# dIRKey.net
KiCad netlist of a schematic drawn in EAGLE
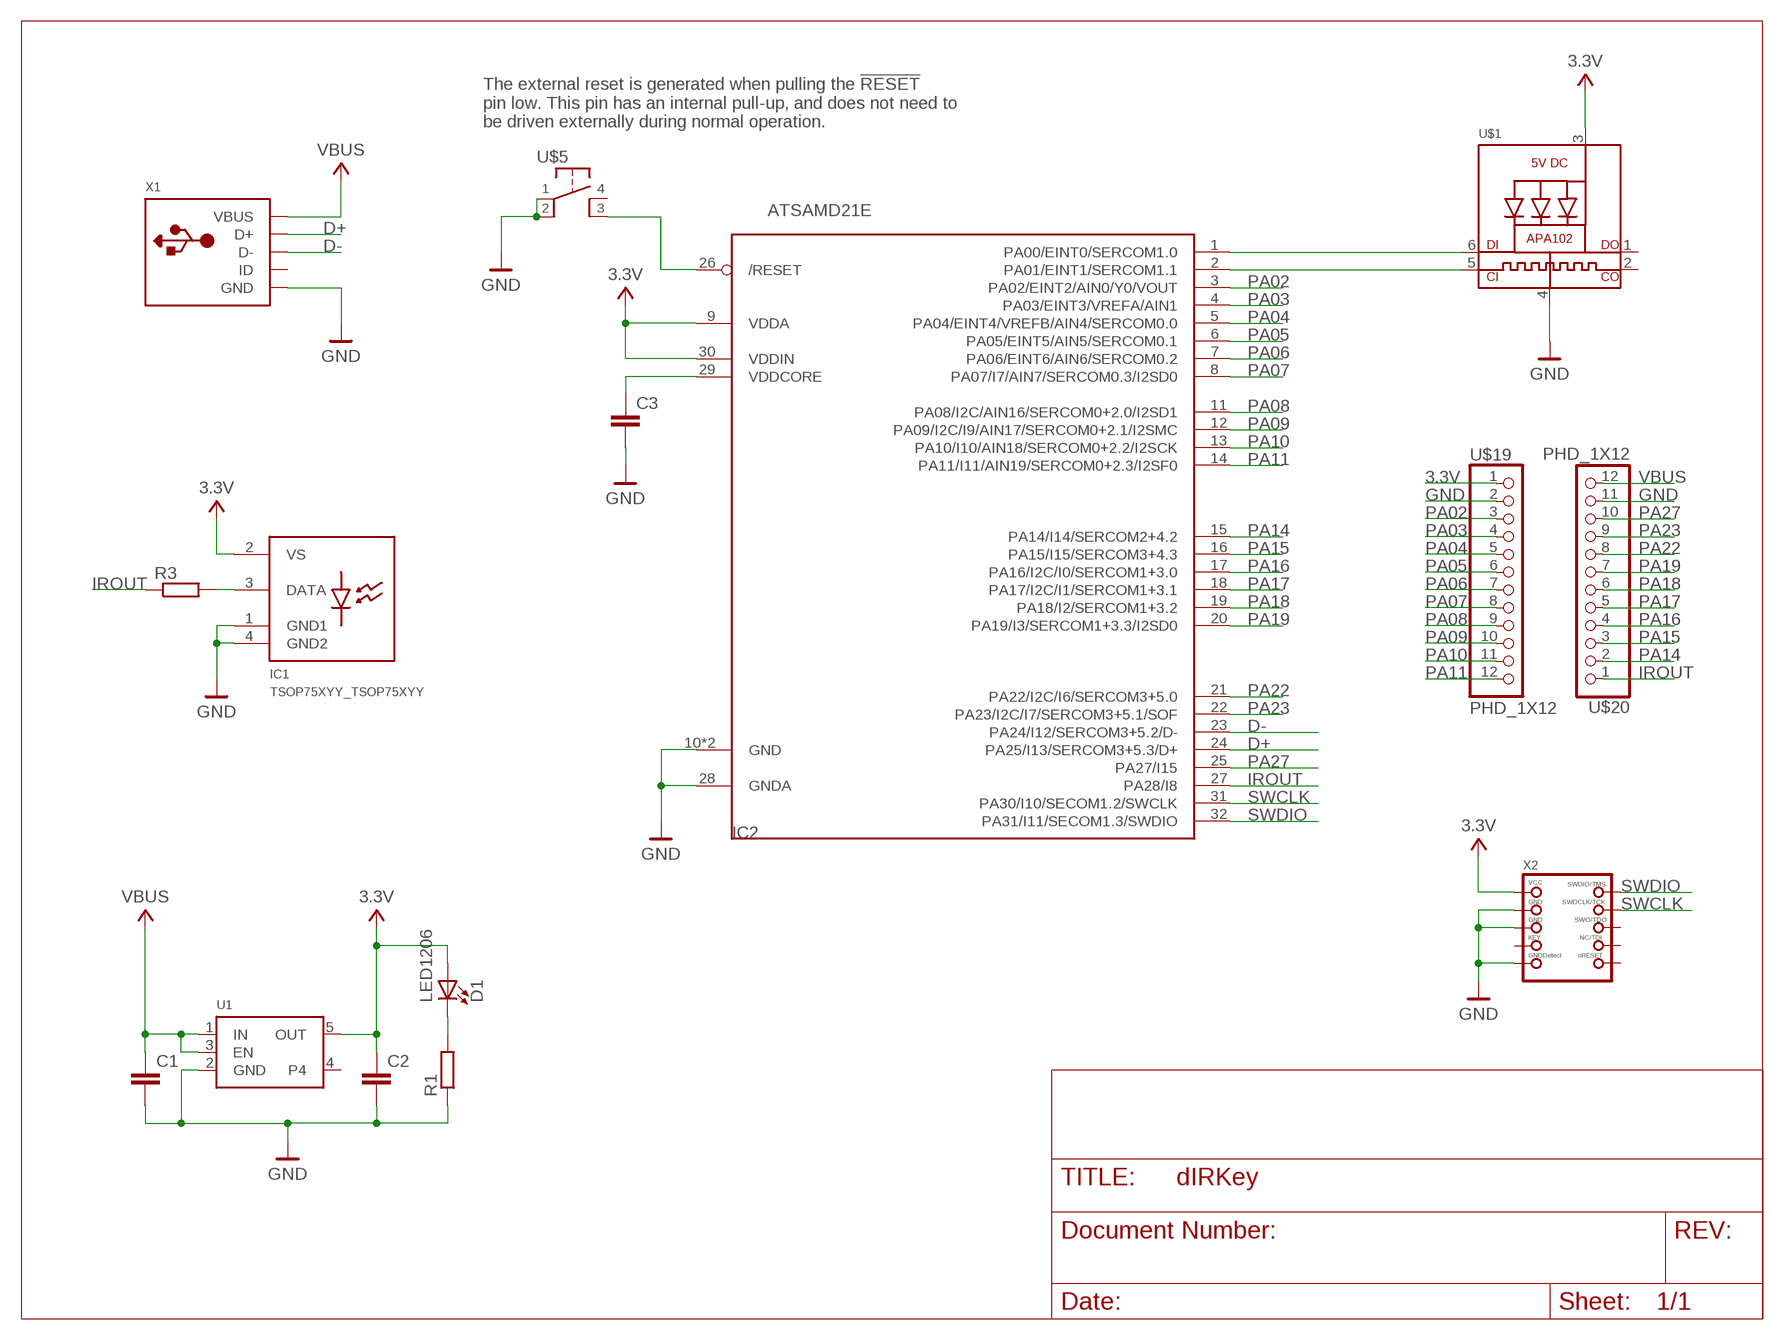
[diagram p0: schematic, sheet 1]

(export (version "E")
  (design (tool "Eeschema 10.0.6"))
  (components
    (comp (ref "C1")
      (value "C-EUC1206")
      (footprint "eagle-import:C1206")
      (libsource (lib "eagle-import") (part "C-EUC1206"))
    )
    (comp (ref "C2")
      (value "C-EUC1206")
      (footprint "eagle-import:C1206")
      (libsource (lib "eagle-import") (part "C-EUC1206"))
    )
    (comp (ref "C3")
      (value "C-EUC1206")
      (footprint "eagle-import:C1206")
      (libsource (lib "eagle-import") (part "C-EUC1206"))
    )
    (comp (ref "D1")
      (value "LED1206")
      (footprint "eagle-import:LED1206")
      (libsource (lib "eagle-import") (part "LED1206"))
    )
    (comp (ref "IC1")
      (value "TSOP75XYY_TSOP75XYY")
      (footprint "eagle-import:TSOP75XYY_TSOP75XYY")
      (libsource (lib "eagle-import") (part "TSOP75XYY_TSOP75XYY"))
    )
    (comp (ref "IC2")
      (value "ATSAMD21E")
      (footprint "eagle-import:QFN32_5MM")
      (libsource (lib "eagle-import") (part "ATSAMD21E"))
    )
    (comp (ref "R1")
      (value "R-EU_R1206")
      (footprint "eagle-import:R1206")
      (libsource (lib "eagle-import") (part "R-EU_R1206"))
    )
    (comp (ref "R3")
      (value "R-EU_R1206")
      (footprint "eagle-import:R1206")
      (libsource (lib "eagle-import") (part "R-EU_R1206"))
    )
    (comp (ref "U$1")
      (value "DOTSTAR_APA1022020")
      (footprint "eagle-import:APA102_2020")
      (libsource (lib "eagle-import") (part "DOTSTAR_APA1022020"))
    )
    (comp (ref "U$5")
      (value "PTS647")
      (footprint "eagle-import:PTS647")
      (libsource (lib "eagle-import") (part "PTS647"))
    )
    (comp (ref "U$19")
      (value "PHD_1X12")
      (footprint "eagle-import:PHD_1X12")
      (libsource (lib "eagle-import") (part "PHD_1X12"))
    )
    (comp (ref "U$20")
      (value "PHD_1X12")
      (footprint "eagle-import:PHD_1X12")
      (libsource (lib "eagle-import") (part "PHD_1X12"))
    )
    (comp (ref "U1")
      (value "AP2112K")
      (footprint "eagle-import:SOT23-5")
      (libsource (lib "eagle-import") (part "AP2112K"))
    )
    (comp (ref "X1")
      (value "USB_MICRO_BMICRO_20329")
      (footprint "eagle-import:USB_MICRO_B")
      (libsource (lib "eagle-import") (part "USB_MICRO_BMICRO_20329"))
    )
    (comp (ref "X2")
      (value "SWD_2X5")
      (footprint "eagle-import:SWD_MINI")
      (libsource (lib "eagle-import") (part "SWD_2X5"))
    )
  )
  (nets
    (net (code "1") (name "/D+") (class "Default")
      (node (ref "IC2") (pin "24") (pinfunction "PA25/I13/SERCOM3+5.3/D+_24") (pintype "bidirectional"))
      (node (ref "X1") (pin "D+") (pinfunction "D+_D+") (pintype "bidirectional"))
    )
    (net (code "2") (name "/D-") (class "Default")
      (node (ref "IC2") (pin "23") (pinfunction "PA24/I12/SERCOM3+5.2/D-_23") (pintype "bidirectional"))
      (node (ref "X1") (pin "D-") (pinfunction "D-_D-") (pintype "bidirectional"))
    )
    (net (code "3") (name "/IROUT") (class "Default")
      (node (ref "IC2") (pin "27") (pinfunction "PA28/I8_27") (pintype "bidirectional"))
      (node (ref "R3") (pin "1") (pinfunction "1_1") (pintype "passive"))
      (node (ref "U$20") (pin "1") (pinfunction "1_1") (pintype "passive"))
    )
    (net (code "4") (name "/PA02") (class "Default")
      (node (ref "IC2") (pin "3") (pinfunction "PA02/EINT2/AIN0/Y0/VOUT_3") (pintype "bidirectional"))
      (node (ref "U$19") (pin "3") (pinfunction "3_3") (pintype "passive"))
    )
    (net (code "5") (name "/PA03") (class "Default")
      (node (ref "IC2") (pin "4") (pinfunction "PA03/EINT3/VREFA/AIN1_4") (pintype "bidirectional"))
      (node (ref "U$19") (pin "4") (pinfunction "4_4") (pintype "passive"))
    )
    (net (code "6") (name "/PA04") (class "Default")
      (node (ref "IC2") (pin "5") (pinfunction "PA04/EINT4/VREFB/AIN4/SERCOM0.0_5") (pintype "bidirectional"))
      (node (ref "U$19") (pin "5") (pinfunction "5_5") (pintype "passive"))
    )
    (net (code "7") (name "/PA05") (class "Default")
      (node (ref "IC2") (pin "6") (pinfunction "PA05/EINT5/AIN5/SERCOM0.1_6") (pintype "bidirectional"))
      (node (ref "U$19") (pin "6") (pinfunction "6_6") (pintype "passive"))
    )
    (net (code "8") (name "/PA06") (class "Default")
      (node (ref "IC2") (pin "7") (pinfunction "PA06/EINT6/AIN6/SERCOM0.2_7") (pintype "bidirectional"))
      (node (ref "U$19") (pin "7") (pinfunction "7_7") (pintype "passive"))
    )
    (net (code "9") (name "/PA07") (class "Default")
      (node (ref "IC2") (pin "8") (pinfunction "PA07/I7/AIN7/SERCOM0.3/I2SD0_8") (pintype "bidirectional"))
      (node (ref "U$19") (pin "8") (pinfunction "8_8") (pintype "passive"))
    )
    (net (code "10") (name "/PA08") (class "Default")
      (node (ref "IC2") (pin "11") (pinfunction "PA08/I2C/AIN16/SERCOM0+2.0/I2SD1_11") (pintype "bidirectional"))
      (node (ref "U$19") (pin "9") (pinfunction "9_9") (pintype "passive"))
    )
    (net (code "11") (name "/PA09") (class "Default")
      (node (ref "IC2") (pin "12") (pinfunction "PA09/I2C/I9/AIN17/SERCOM0+2.1/I2SMC_12") (pintype "bidirectional"))
      (node (ref "U$19") (pin "10") (pinfunction "10_10") (pintype "passive"))
    )
    (net (code "12") (name "/PA10") (class "Default")
      (node (ref "IC2") (pin "13") (pinfunction "PA10/I10/AIN18/SERCOM0+2.2/I2SCK_13") (pintype "bidirectional"))
      (node (ref "U$19") (pin "11") (pinfunction "11_11") (pintype "passive"))
    )
    (net (code "13") (name "/PA11") (class "Default")
      (node (ref "IC2") (pin "14") (pinfunction "PA11/I11/AIN19/SERCOM0+2.3/I2SF0_14") (pintype "bidirectional"))
      (node (ref "U$19") (pin "12") (pinfunction "12_12") (pintype "passive"))
    )
    (net (code "14") (name "/PA14") (class "Default")
      (node (ref "IC2") (pin "15") (pinfunction "PA14/I14/SERCOM2+4.2_15") (pintype "bidirectional"))
      (node (ref "U$20") (pin "2") (pinfunction "2_2") (pintype "passive"))
    )
    (net (code "15") (name "/PA15") (class "Default")
      (node (ref "IC2") (pin "16") (pinfunction "PA15/I15/SERCOM3+4.3_16") (pintype "bidirectional"))
      (node (ref "U$20") (pin "3") (pinfunction "3_3") (pintype "passive"))
    )
    (net (code "16") (name "/PA16") (class "Default")
      (node (ref "IC2") (pin "17") (pinfunction "PA16/I2C/I0/SERCOM1+3.0_17") (pintype "bidirectional"))
      (node (ref "U$20") (pin "4") (pinfunction "4_4") (pintype "passive"))
    )
    (net (code "17") (name "/PA17") (class "Default")
      (node (ref "IC2") (pin "18") (pinfunction "PA17/I2C/I1/SERCOM1+3.1_18") (pintype "bidirectional"))
      (node (ref "U$20") (pin "5") (pinfunction "5_5") (pintype "passive"))
    )
    (net (code "18") (name "/PA18") (class "Default")
      (node (ref "IC2") (pin "19") (pinfunction "PA18/I2/SERCOM1+3.2_19") (pintype "bidirectional"))
      (node (ref "U$20") (pin "6") (pinfunction "6_6") (pintype "passive"))
    )
    (net (code "19") (name "/PA19") (class "Default")
      (node (ref "IC2") (pin "20") (pinfunction "PA19/I3/SERCOM1+3.3/I2SD0_20") (pintype "bidirectional"))
      (node (ref "U$20") (pin "7") (pinfunction "7_7") (pintype "passive"))
    )
    (net (code "20") (name "/PA22") (class "Default")
      (node (ref "IC2") (pin "21") (pinfunction "PA22/I2C/I6/SERCOM3+5.0_21") (pintype "bidirectional"))
      (node (ref "U$20") (pin "8") (pinfunction "8_8") (pintype "passive"))
    )
    (net (code "21") (name "/PA23") (class "Default")
      (node (ref "IC2") (pin "22") (pinfunction "PA23/I2C/I7/SERCOM3+5.1/SOF_22") (pintype "bidirectional"))
      (node (ref "U$20") (pin "9") (pinfunction "9_9") (pintype "passive"))
    )
    (net (code "22") (name "/PA27") (class "Default")
      (node (ref "IC2") (pin "25") (pinfunction "PA27/I15_25") (pintype "bidirectional"))
      (node (ref "U$20") (pin "10") (pinfunction "10_10") (pintype "passive"))
    )
    (net (code "23") (name "/SWCLK") (class "Default")
      (node (ref "IC2") (pin "31") (pinfunction "PA30/I10/SECOM1.2/SWCLK_31") (pintype "bidirectional"))
      (node (ref "X2") (pin "4") (pinfunction "SWDCLK_4") (pintype "bidirectional"))
    )
    (net (code "24") (name "/SWDIO") (class "Default")
      (node (ref "IC2") (pin "32") (pinfunction "PA31/I11/SECOM1.3/SWDIO_32") (pintype "bidirectional"))
      (node (ref "X2") (pin "2") (pinfunction "SWDIO_2") (pintype "bidirectional"))
    )
    (net (code "25") (name "3.3V") (class "Default")
      (node (ref "C2") (pin "1") (pinfunction "1_1") (pintype "passive"))
      (node (ref "D1") (pin "2") (pinfunction "A_2") (pintype "passive"))
      (node (ref "IC1") (pin "2") (pinfunction "VS_2") (pintype "passive"))
      (node (ref "IC2") (pin "30") (pinfunction "VDDIN_30") (pintype "power_in"))
      (node (ref "IC2") (pin "9") (pinfunction "VDDA_9") (pintype "power_in"))
      (node (ref "U$1") (pin "3") (pinfunction "VDD_3") (pintype "power_in"))
      (node (ref "U$19") (pin "1") (pinfunction "1_1") (pintype "passive"))
      (node (ref "U1") (pin "5") (pinfunction "OUT_5") (pintype "power_in"))
      (node (ref "X2") (pin "1") (pinfunction "VCC_1") (pintype "power_in"))
    )
    (net (code "26") (name "GND") (class "Default")
      (node (ref "C1") (pin "2") (pinfunction "2_2") (pintype "passive"))
      (node (ref "C2") (pin "2") (pinfunction "2_2") (pintype "passive"))
      (node (ref "C3") (pin "2") (pinfunction "2_2") (pintype "passive"))
      (node (ref "IC1") (pin "1") (pinfunction "GND1_1") (pintype "passive"))
      (node (ref "IC1") (pin "4") (pinfunction "GND2_4") (pintype "passive"))
      (node (ref "IC2") (pin "10") (pinfunction "GND_10") (pintype "power_in"))
      (node (ref "IC2") (pin "28") (pinfunction "GNDA_28") (pintype "power_in"))
      (node (ref "IC2") (pin "33") (pinfunction "GND_33") (pintype "power_in"))
      (node (ref "R1") (pin "1") (pinfunction "1_1") (pintype "passive"))
      (node (ref "U$1") (pin "4") (pinfunction "GND_4") (pintype "power_in"))
      (node (ref "U$19") (pin "2") (pinfunction "2_2") (pintype "passive"))
      (node (ref "U$20") (pin "11") (pinfunction "11_11") (pintype "passive"))
      (node (ref "U$5") (pin "1") (pinfunction "1_1") (pintype "bidirectional"))
      (node (ref "U$5") (pin "2") (pinfunction "2_2") (pintype "bidirectional"))
      (node (ref "U1") (pin "2") (pinfunction "GND_2") (pintype "power_in"))
      (node (ref "X1") (pin "BASE@1") (pinfunction "GND_BASE@1") (pintype "power_in"))
      (node (ref "X1") (pin "BASE@2") (pinfunction "GND_BASE@2") (pintype "power_in"))
      (node (ref "X1") (pin "GND") (pinfunction "GND_GND") (pintype "power_in"))
      (node (ref "X1") (pin "SPRT@1") (pinfunction "GND_SPRT@1") (pintype "power_in"))
      (node (ref "X1") (pin "SPRT@2") (pinfunction "GND_SPRT@2") (pintype "power_in"))
      (node (ref "X1") (pin "SPRT@3") (pinfunction "GND_SPRT@3") (pintype "power_in"))
      (node (ref "X1") (pin "SPRT@4") (pinfunction "GND_SPRT@4") (pintype "power_in"))
      (node (ref "X2") (pin "3") (pinfunction "GND_3") (pintype "power_in"))
      (node (ref "X2") (pin "5") (pinfunction "GND_5") (pintype "power_in"))
      (node (ref "X2") (pin "9") (pinfunction "GNDDETECT_9") (pintype "bidirectional"))
    )
    (net (code "27") (name "Net-(D1-C)") (class "Default")
      (node (ref "D1") (pin "1") (pinfunction "C_1") (pintype "passive"))
      (node (ref "R1") (pin "2") (pinfunction "2_2") (pintype "passive"))
    )
    (net (code "28") (name "Net-(IC1-DATA)") (class "Default")
      (node (ref "IC1") (pin "3") (pinfunction "DATA_3") (pintype "output"))
      (node (ref "R3") (pin "2") (pinfunction "2_2") (pintype "passive"))
    )
    (net (code "29") (name "Net-(IC2-PA00{slash}EINT0{slash}SERCOM1.0)") (class "Default")
      (node (ref "IC2") (pin "1") (pinfunction "PA00/EINT0/SERCOM1.0_1") (pintype "bidirectional"))
      (node (ref "U$1") (pin "6") (pinfunction "DI_6") (pintype "input"))
    )
    (net (code "30") (name "Net-(IC2-PA01{slash}EINT1{slash}SERCOM1.1)") (class "Default")
      (node (ref "IC2") (pin "2") (pinfunction "PA01/EINT1/SERCOM1.1_2") (pintype "bidirectional"))
      (node (ref "U$1") (pin "5") (pinfunction "CKI_5") (pintype "input"))
    )
    (net (code "31") (name "Net-(IC2-VDDCORE)") (class "Default")
      (node (ref "C3") (pin "1") (pinfunction "1_1") (pintype "passive"))
      (node (ref "IC2") (pin "29") (pinfunction "VDDCORE_29") (pintype "power_in"))
    )
    (net (code "32") (name "Net-(IC2-{slash}RESET)") (class "Default")
      (node (ref "IC2") (pin "26") (pinfunction "/RESET_26") (pintype "bidirectional"))
      (node (ref "U$5") (pin "3") (pinfunction "3_3") (pintype "bidirectional"))
    )
    (net (code "33") (name "VBUS") (class "Default")
      (node (ref "C1") (pin "1") (pinfunction "1_1") (pintype "passive"))
      (node (ref "U$20") (pin "12") (pinfunction "12_12") (pintype "passive"))
      (node (ref "U1") (pin "1") (pinfunction "IN_1") (pintype "power_in"))
      (node (ref "U1") (pin "3") (pinfunction "EN_3") (pintype "input"))
      (node (ref "X1") (pin "VBUS") (pinfunction "VBUS_VBUS") (pintype "power_in"))
    )
    (net (code "34") (name "unconnected-(U$1-CKO-Pad2)") (class "Default")
      (node (ref "U$1") (pin "2") (pinfunction "CKO_2") (pintype "output"))
    )
    (net (code "35") (name "unconnected-(U$1-DO-Pad1)") (class "Default")
      (node (ref "U$1") (pin "1") (pinfunction "DO_1") (pintype "output"))
    )
    (net (code "36") (name "unconnected-(U$5-Pad4)") (class "Default")
      (node (ref "U$5") (pin "4") (pinfunction "4_4") (pintype "bidirectional"))
    )
    (net (code "37") (name "unconnected-(U1-P4-Pad4)") (class "Default")
      (node (ref "U1") (pin "4") (pinfunction "P4_4") (pintype "bidirectional"))
    )
    (net (code "38") (name "unconnected-(X1-PadID)") (class "Default")
      (node (ref "X1") (pin "ID") (pinfunction "ID_ID") (pintype "bidirectional"))
    )
    (net (code "39") (name "unconnected-(X2-KEY-Pad7)") (class "Default")
      (node (ref "X2") (pin "7") (pinfunction "KEY_7") (pintype "bidirectional"))
    )
    (net (code "40") (name "unconnected-(X2-NRESET-Pad10)") (class "Default")
      (node (ref "X2") (pin "10") (pinfunction "NRESET_10") (pintype "bidirectional"))
    )
    (net (code "41") (name "unconnected-(X2-SWO-Pad6)") (class "Default")
      (node (ref "X2") (pin "6") (pinfunction "SWO_6") (pintype "bidirectional"))
    )
    (net (code "42") (name "unconnected-(X2-TDI-Pad8)") (class "Default")
      (node (ref "X2") (pin "8") (pinfunction "TDI_8") (pintype "bidirectional"))
    )
  )
)
